# SparkFun_Air_Quality_ENS160_Qwiic_Micro.net
KiCad netlist of a schematic drawn in EAGLE
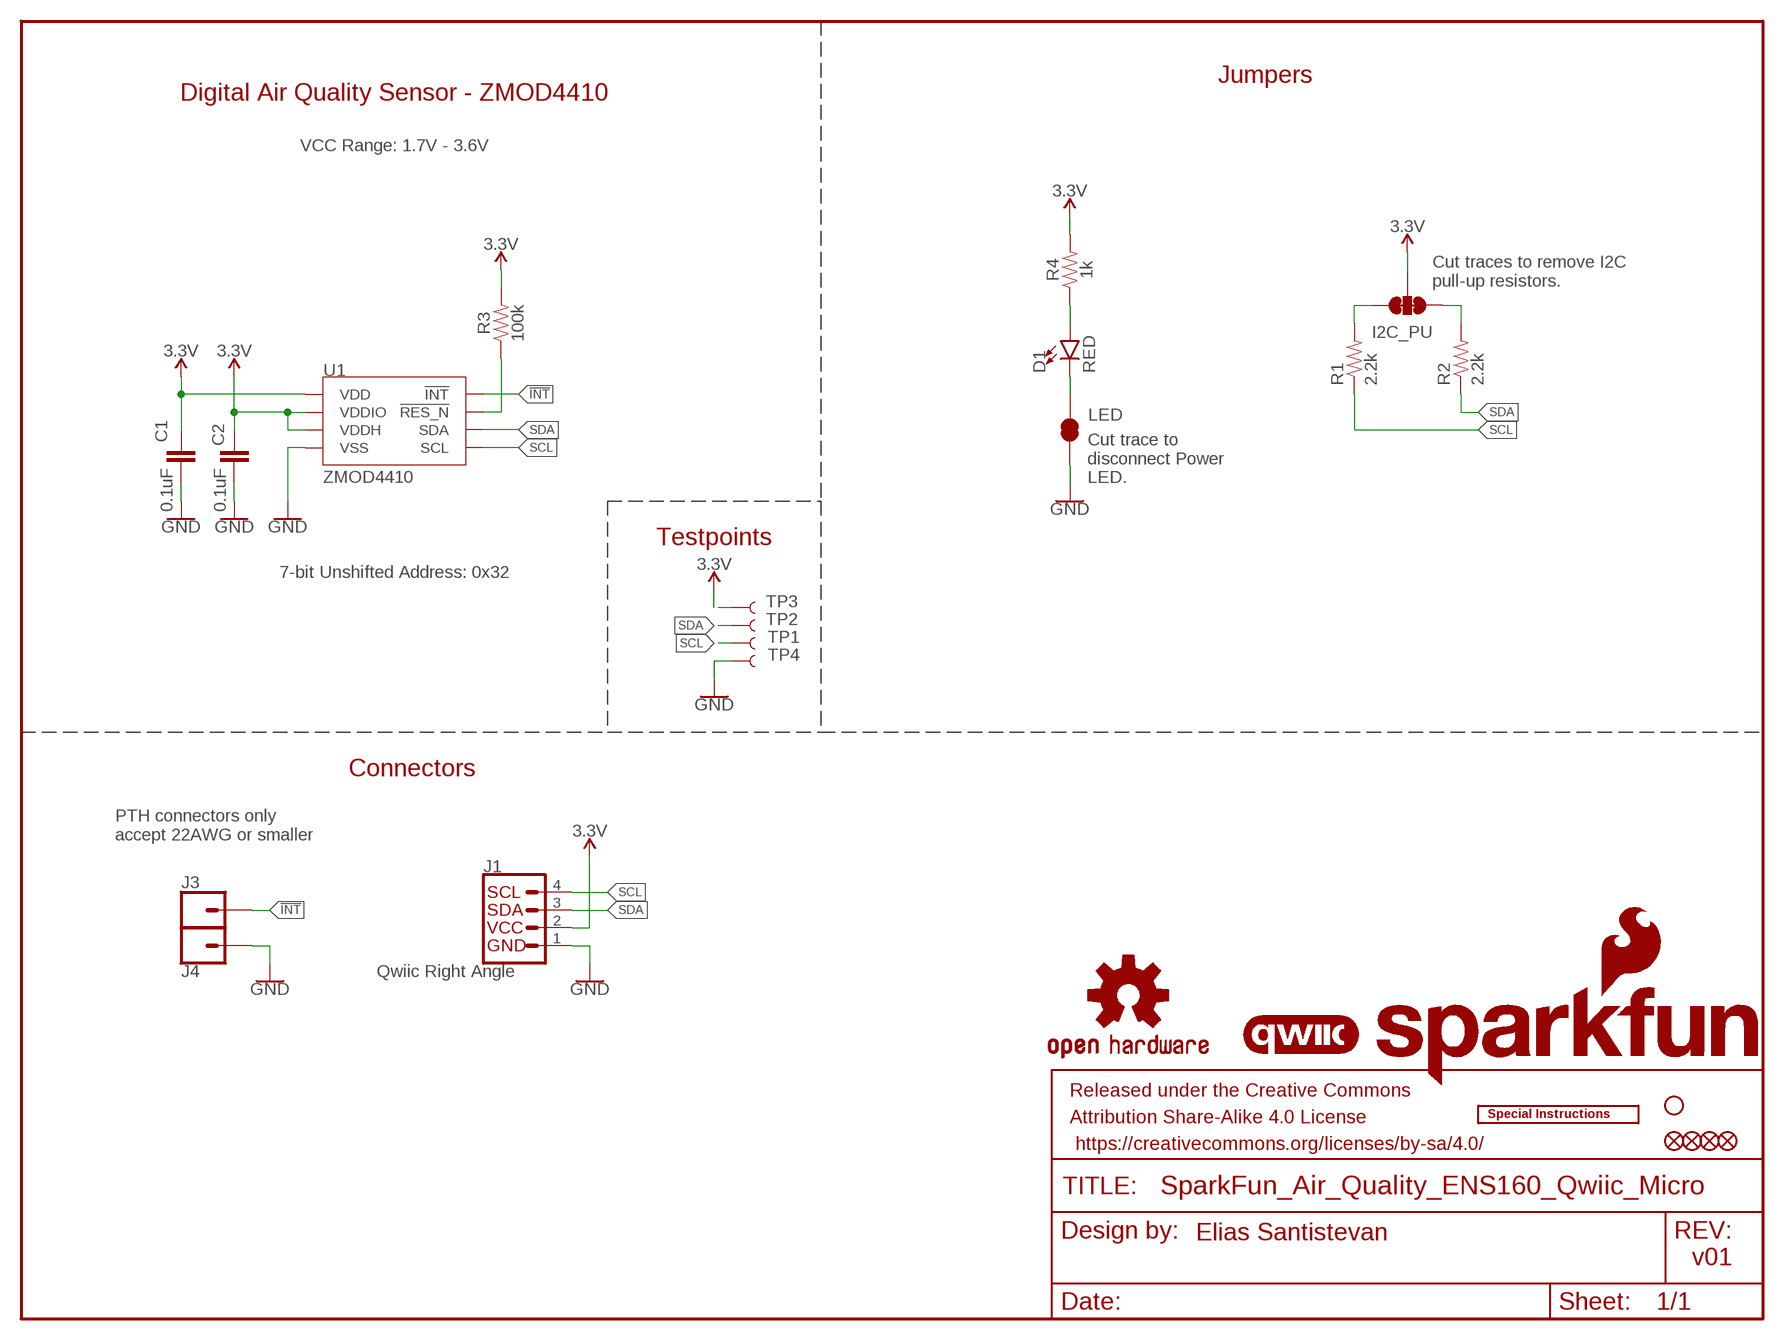
[diagram p0: schematic, sheet 1]

(export (version "E")
  (design (tool "Eeschema 10.0.6"))
  (components
    (comp (ref "C1")
      (value "0.1uF")
      (footprint "eagle-import:0402-TIGHT")
      (libsource (lib "eagle-import") (part "0.1UF-0402T-16V-10%"))
    )
    (comp (ref "C2")
      (value "0.1uF")
      (footprint "eagle-import:0402-TIGHT")
      (libsource (lib "eagle-import") (part "0.1UF-0402T-16V-10%"))
    )
    (comp (ref "D1")
      (value "RED")
      (footprint "eagle-import:LED-0402")
      (libsource (lib "eagle-import") (part "LED-RED_0402"))
    )
    (comp (ref "FD1")
      (value "FIDUCIALUFIDUCIAL")
      (footprint "eagle-import:FIDUCIAL-MICRO")
      (libsource (lib "eagle-import") (part "FIDUCIALUFIDUCIAL"))
    )
    (comp (ref "FD2")
      (value "FIDUCIALUFIDUCIAL")
      (footprint "eagle-import:FIDUCIAL-MICRO")
      (libsource (lib "eagle-import") (part "FIDUCIALUFIDUCIAL"))
    )
    (comp (ref "FID1")
      (value "FIDUCIALUFIDUCIAL")
      (footprint "eagle-import:FIDUCIAL-MICRO")
      (libsource (lib "eagle-import") (part "FIDUCIALUFIDUCIAL"))
    )
    (comp (ref "FID2")
      (value "FIDUCIALUFIDUCIAL")
      (footprint "eagle-import:FIDUCIAL-MICRO")
      (libsource (lib "eagle-import") (part "FIDUCIALUFIDUCIAL"))
    )
    (comp (ref "FRAME1")
      (value "FRAME-LETTER")
      (footprint "eagle-import:CREATIVE_COMMONS")
      (fields (field (name "DESIGNER") "Elias Santistevan"))
      (libsource (lib "eagle-import") (part "FRAME-LETTER"))
    )
    (comp (ref "I2C_PU")
      (value "S_MODE")
      (footprint "eagle-import:SMT-JUMPER_3_2-NC_TRACE_SILK")
      (libsource (lib "eagle-import") (part "JUMPER-SMT_3_2-NC_TRACE_SILK"))
    )
    (comp (ref "J1")
      (value "Qwiic Right Angle")
      (footprint "eagle-import:JST04_1MM_RA")
      (libsource (lib "eagle-import") (part "I2C_STANDARDQWIIC"))
    )
    (comp (ref "J3")
      (value "CONN_01_1MM")
      (footprint "eagle-import:1X01_1MM_NO_SILK")
      (libsource (lib "eagle-import") (part "CONN_01_1MM"))
    )
    (comp (ref "J4")
      (value "CONN_01_1MM")
      (footprint "eagle-import:1X01_1MM_NO_SILK")
      (libsource (lib "eagle-import") (part "CONN_01_1MM"))
    )
    (comp (ref "LED")
      (value "JUMPER-SMT_2_NC_TRACE_SILK")
      (footprint "eagle-import:SMT-JUMPER_2_NC_TRACE_SILK")
      (libsource (lib "eagle-import") (part "JUMPER-SMT_2_NC_TRACE_SILK"))
    )
    (comp (ref "LOGO1")
      (value "QWIIC_LOGO_3MM")
      (footprint "eagle-import:QWIIC_3MM")
      (libsource (lib "eagle-import") (part "QWIIC_LOGO_3MM"))
    )
    (comp (ref "LOGO2")
      (value "OSHW-LOGOMINI")
      (footprint "eagle-import:OSHW-LOGO-MINI")
      (libsource (lib "eagle-import") (part "OSHW-LOGOMINI"))
    )
    (comp (ref "LOGO3")
      (value "SFE_LOGO_NAME_FLAMEBLANK")
      (footprint "eagle-import:BLANK")
      (libsource (lib "eagle-import") (part "SFE_LOGO_NAME_FLAMEBLANK"))
    )
    (comp (ref "LOGO4")
      (value "SPECIAL_INSTRUCTIONS-PRODUCTION")
      (footprint "eagle-import:PRODUCTION_INSTRUCTIONS")
      (libsource (lib "eagle-import") (part "SPECIAL_INSTRUCTIONS-PRODUCTION"))
    )
    (comp (ref "R1")
      (value "2.2k")
      (footprint "eagle-import:0402-TIGHT")
      (libsource (lib "eagle-import") (part "2.2KOHM-0402T-1/16W-1%"))
    )
    (comp (ref "R2")
      (value "2.2k")
      (footprint "eagle-import:0402-TIGHT")
      (libsource (lib "eagle-import") (part "2.2KOHM-0402T-1/16W-1%"))
    )
    (comp (ref "R3")
      (value "100k")
      (footprint "eagle-import:0402-TIGHT")
      (libsource (lib "eagle-import") (part "100KOHM-0402T-1/16W-1%"))
    )
    (comp (ref "R4")
      (value "1k")
      (footprint "eagle-import:0402-TIGHT")
      (libsource (lib "eagle-import") (part "1KOHM-0402T-1/16W-1%"))
    )
    (comp (ref "STANDOFF1")
      (value "STAND-OFFTIGHT")
      (footprint "eagle-import:STAND-OFF-TIGHT")
      (libsource (lib "eagle-import") (part "STAND-OFFTIGHT"))
    )
    (comp (ref "TP1")
      (value "TEST-POINT3")
      (footprint "eagle-import:PAD.03X.03")
      (libsource (lib "eagle-import") (part "TEST-POINT3"))
    )
    (comp (ref "TP2")
      (value "TEST-POINT3")
      (footprint "eagle-import:PAD.03X.03")
      (libsource (lib "eagle-import") (part "TEST-POINT3"))
    )
    (comp (ref "TP3")
      (value "TEST-POINT3")
      (footprint "eagle-import:PAD.03X.03")
      (libsource (lib "eagle-import") (part "TEST-POINT3"))
    )
    (comp (ref "TP4")
      (value "TEST-POINT3")
      (footprint "eagle-import:PAD.03X.03")
      (libsource (lib "eagle-import") (part "TEST-POINT3"))
    )
    (comp (ref "U1")
      (value "ZMOD4410")
      (footprint "eagle-import:LGA-12")
      (libsource (lib "eagle-import") (part "ZMOD4410"))
    )
  )
  (nets
    (net (code "1") (name "/~{INT}") (class "Default")
      (node (ref "J3") (pin "1") (pinfunction "1_1") (pintype "passive"))
      (node (ref "U1") (pin "P3") (pinfunction "~{INT}_P3") (pintype "bidirectional"))
    )
    (net (code "2") (name "3.3V") (class "Default")
      (node (ref "C1") (pin "1") (pinfunction "1_1") (pintype "passive"))
      (node (ref "C2") (pin "1") (pinfunction "1_1") (pintype "passive"))
      (node (ref "I2C_PU") (pin "2") (pinfunction "2_2") (pintype "passive"))
      (node (ref "J1") (pin "2") (pinfunction "2_2") (pintype "power_in"))
      (node (ref "R3") (pin "2") (pinfunction "2_2") (pintype "passive"))
      (node (ref "R4") (pin "2") (pinfunction "2_2") (pintype "passive"))
      (node (ref "TP3") (pin "1") (pinfunction "1_1") (pintype "bidirectional"))
      (node (ref "U1") (pin "P10") (pinfunction "VDDH_P10") (pintype "power_in"))
      (node (ref "U1") (pin "P12") (pinfunction "VDDIO_P12") (pintype "power_in"))
      (node (ref "U1") (pin "P5") (pinfunction "VDD_P5") (pintype "power_in"))
    )
    (net (code "3") (name "GND") (class "Default")
      (node (ref "C1") (pin "2") (pinfunction "2_2") (pintype "passive"))
      (node (ref "C2") (pin "2") (pinfunction "2_2") (pintype "passive"))
      (node (ref "J1") (pin "1") (pinfunction "1_1") (pintype "power_in"))
      (node (ref "J4") (pin "1") (pinfunction "1_1") (pintype "passive"))
      (node (ref "LED") (pin "1") (pinfunction "1_1") (pintype "passive"))
      (node (ref "TP4") (pin "1") (pinfunction "1_1") (pintype "bidirectional"))
      (node (ref "U1") (pin "P6") (pinfunction "VSS_P6") (pintype "power_in"))
      (node (ref "U1") (pin "P7") (pinfunction "VSS_P7") (pintype "power_in"))
      (node (ref "U1") (pin "P9") (pinfunction "VSS_P9") (pintype "power_in"))
    )
    (net (code "4") (name "Net-(D1-PadA)") (class "Default")
      (node (ref "D1") (pin "A") (pinfunction "A_A") (pintype "passive"))
      (node (ref "R4") (pin "1") (pinfunction "1_1") (pintype "passive"))
    )
    (net (code "5") (name "Net-(D1-PadC)") (class "Default")
      (node (ref "D1") (pin "C") (pinfunction "C_C") (pintype "passive"))
      (node (ref "LED") (pin "2") (pinfunction "2_2") (pintype "passive"))
    )
    (net (code "6") (name "Net-(I2C_PU-Pad1)") (class "Default")
      (node (ref "I2C_PU") (pin "1") (pinfunction "1_1") (pintype "passive"))
      (node (ref "R1") (pin "2") (pinfunction "2_2") (pintype "passive"))
    )
    (net (code "7") (name "Net-(I2C_PU-Pad3)") (class "Default")
      (node (ref "I2C_PU") (pin "3") (pinfunction "3_3") (pintype "passive"))
      (node (ref "R2") (pin "2") (pinfunction "2_2") (pintype "passive"))
    )
    (net (code "8") (name "Net-(U1-~{RES_N})") (class "Default")
      (node (ref "R3") (pin "1") (pinfunction "1_1") (pintype "passive"))
      (node (ref "U1") (pin "P11") (pinfunction "~{RES_N}_P11") (pintype "bidirectional"))
    )
    (net (code "9") (name "SCL") (class "Default")
      (node (ref "J1") (pin "4") (pinfunction "4_4") (pintype "passive"))
      (node (ref "R1") (pin "1") (pinfunction "1_1") (pintype "passive"))
      (node (ref "TP1") (pin "1") (pinfunction "1_1") (pintype "bidirectional"))
      (node (ref "U1") (pin "P1") (pinfunction "SCL_P1") (pintype "bidirectional"))
    )
    (net (code "10") (name "SDA") (class "Default")
      (node (ref "J1") (pin "3") (pinfunction "3_3") (pintype "passive"))
      (node (ref "R2") (pin "1") (pinfunction "1_1") (pintype "passive"))
      (node (ref "TP2") (pin "1") (pinfunction "1_1") (pintype "bidirectional"))
      (node (ref "U1") (pin "P2") (pinfunction "SDA_P2") (pintype "bidirectional"))
    )
  )
)
